# tb_projekt_rfm12b_board_v1_0.net
KiCad netlist of a schematic drawn in EAGLE
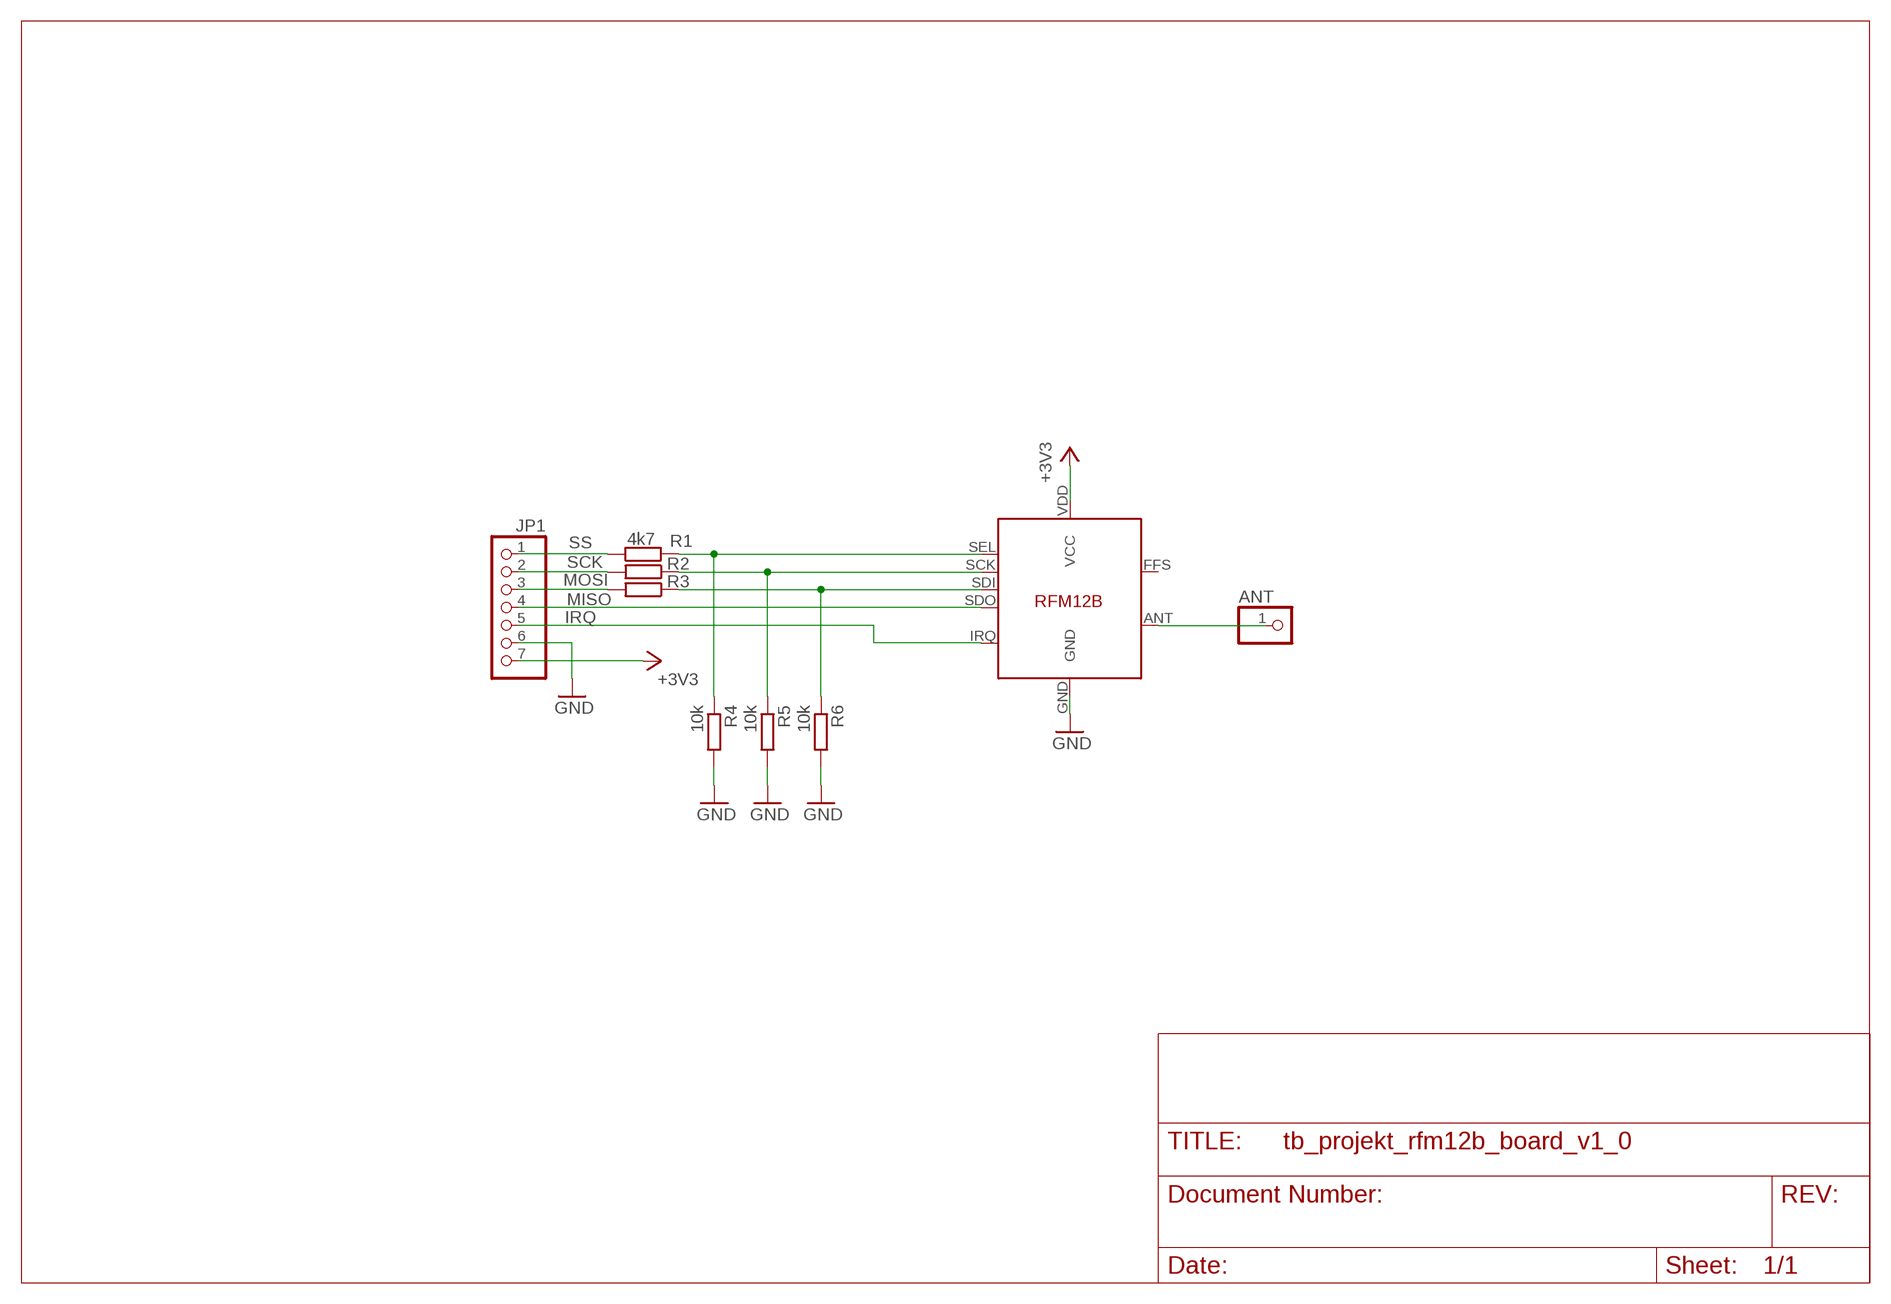
[diagram p0: schematic, sheet 1]

(export (version "E")
  (design (tool "Eeschema 10.0.6"))
  (components
    (comp (ref "ANT")
      (value "PINHD-1X1")
      (footprint "eagle-import:1X01")
      (libsource (lib "eagle-import") (part "PINHD-1X1"))
    )
    (comp (ref "IC1")
      (value "RFM12B")
      (footprint "eagle-import:RFM12B")
      (libsource (lib "eagle-import") (part "RFM12B"))
    )
    (comp (ref "JP1")
      (value "PINHD-1X7")
      (footprint "eagle-import:1X07")
      (libsource (lib "eagle-import") (part "PINHD-1X7"))
    )
    (comp (ref "R1")
      (value "4k7")
      (footprint "eagle-import:0207_7")
      (libsource (lib "eagle-import") (part "R-EU_0207/7"))
    )
    (comp (ref "R2")
      (value "R-EU_0207/7")
      (footprint "eagle-import:0207_7")
      (libsource (lib "eagle-import") (part "R-EU_0207/7"))
    )
    (comp (ref "R3")
      (value "R-EU_0207/7")
      (footprint "eagle-import:0207_7")
      (libsource (lib "eagle-import") (part "R-EU_0207/7"))
    )
    (comp (ref "R4")
      (value "10k")
      (footprint "eagle-import:0207_7")
      (libsource (lib "eagle-import") (part "R-EU_0207/7"))
    )
    (comp (ref "R5")
      (value "10k")
      (footprint "eagle-import:0207_7")
      (libsource (lib "eagle-import") (part "R-EU_0207/7"))
    )
    (comp (ref "R6")
      (value "10k")
      (footprint "eagle-import:0207_7")
      (libsource (lib "eagle-import") (part "R-EU_0207/7"))
    )
  )
  (nets
    (net (code "1") (name "+3V3") (class "Default")
      (node (ref "IC1") (pin "VDD") (pinfunction "VCC_VDD") (pintype "power_in"))
      (node (ref "JP1") (pin "7") (pinfunction "7_7") (pintype "passive"))
    )
    (net (code "2") (name "/IRQ") (class "Default")
      (node (ref "IC1") (pin "IRQ") (pinfunction "IRQ_IRQ") (pintype "open_collector"))
      (node (ref "JP1") (pin "5") (pinfunction "5_5") (pintype "passive"))
    )
    (net (code "3") (name "/MISO") (class "Default")
      (node (ref "IC1") (pin "SDO") (pinfunction "SDO_SDO") (pintype "output"))
      (node (ref "JP1") (pin "4") (pinfunction "4_4") (pintype "passive"))
    )
    (net (code "4") (name "/MOSI") (class "Default")
      (node (ref "JP1") (pin "3") (pinfunction "3_3") (pintype "passive"))
      (node (ref "R3") (pin "2") (pinfunction "2_2") (pintype "passive"))
    )
    (net (code "5") (name "/SCK") (class "Default")
      (node (ref "JP1") (pin "2") (pinfunction "2_2") (pintype "passive"))
      (node (ref "R2") (pin "2") (pinfunction "2_2") (pintype "passive"))
    )
    (net (code "6") (name "/SS") (class "Default")
      (node (ref "JP1") (pin "1") (pinfunction "1_1") (pintype "passive"))
      (node (ref "R1") (pin "1") (pinfunction "1_1") (pintype "passive"))
    )
    (net (code "7") (name "GND") (class "Default")
      (node (ref "IC1") (pin "GND") (pinfunction "GND_GND") (pintype "power_in"))
      (node (ref "JP1") (pin "6") (pinfunction "6_6") (pintype "passive"))
      (node (ref "R4") (pin "2") (pinfunction "2_2") (pintype "passive"))
      (node (ref "R5") (pin "2") (pinfunction "2_2") (pintype "passive"))
      (node (ref "R6") (pin "2") (pinfunction "2_2") (pintype "passive"))
    )
    (net (code "8") (name "Net-(ANT-Pad1)") (class "Default")
      (node (ref "ANT") (pin "1") (pinfunction "1_1") (pintype "passive"))
      (node (ref "IC1") (pin "ANT") (pinfunction "ANT_ANT") (pintype "passive"))
    )
    (net (code "9") (name "Net-(IC1-PadSCK)") (class "Default")
      (node (ref "IC1") (pin "SCK") (pinfunction "SCK_SCK") (pintype "input"))
      (node (ref "R2") (pin "1") (pinfunction "1_1") (pintype "passive"))
      (node (ref "R5") (pin "1") (pinfunction "1_1") (pintype "passive"))
    )
    (net (code "10") (name "Net-(IC1-PadSDI)") (class "Default")
      (node (ref "IC1") (pin "SDI") (pinfunction "SDI_SDI") (pintype "input"))
      (node (ref "R3") (pin "1") (pinfunction "1_1") (pintype "passive"))
      (node (ref "R6") (pin "1") (pinfunction "1_1") (pintype "passive"))
    )
    (net (code "11") (name "Net-(IC1-PadSEL)") (class "Default")
      (node (ref "IC1") (pin "SEL") (pinfunction "SEL_SEL") (pintype "input"))
      (node (ref "R1") (pin "2") (pinfunction "2_2") (pintype "passive"))
      (node (ref "R4") (pin "1") (pinfunction "1_1") (pintype "passive"))
    )
    (net (code "12") (name "unconnected-(IC1-PadFFS)") (class "Default")
      (node (ref "IC1") (pin "FFS") (pinfunction "FFS_FFS") (pintype "bidirectional"))
    )
  )
)
